# PLL.net
KiCad netlist of a schematic drawn in Altium Designer
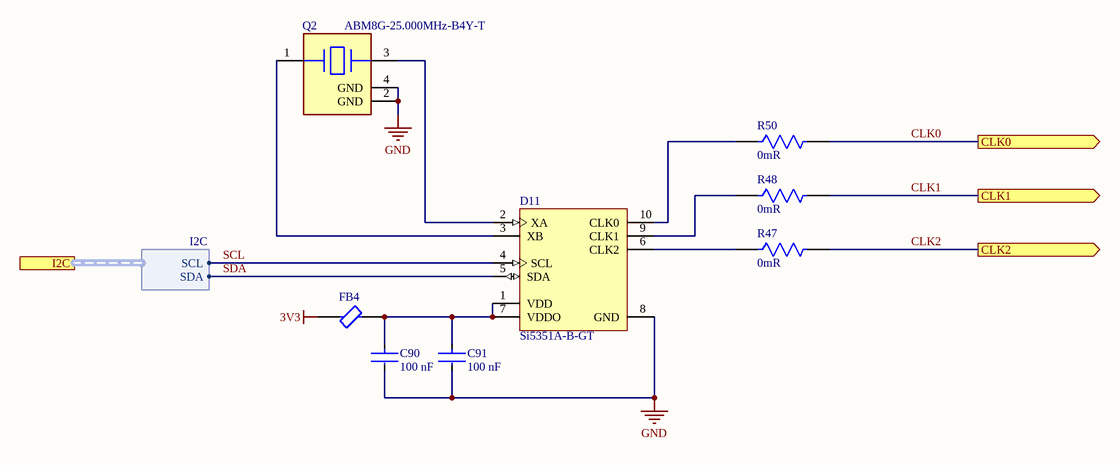
[diagram p0: PLL.SchDoc]

(export (version "E")
  (design (tool "Eeschema 10.0.6"))
  (components
    (comp (ref "C90")
      (value "CC0805KRX7R9BB104")
      (footprint "FP-CC0805-0_85-IPC_A")
      (description "CAP CER 0.1UF 50V X7R 0805")
      (fields (field (name "MANUFACTURER") "Yageo") (field (name "CAPACITANCE") "100 nF"))
      (libsource (lib "zxevo") (part "CMP-2100-03606-3"))
    )
    (comp (ref "C91")
      (value "CC0805KRX7R9BB104")
      (footprint "FP-CC0805-0_85-IPC_A")
      (description "CAP CER 0.1UF 50V X7R 0805")
      (fields (field (name "MANUFACTURER") "Yageo") (field (name "CAPACITANCE") "100 nF"))
      (libsource (lib "zxevo") (part "CMP-2100-03606-3"))
    )
    (comp (ref "D11")
      (value "Si5351A-B-GT")
      (footprint "SLAB-MSOP-10_L")
      (fields
        (field (name "MANUFACTURER") "Silicon Labs")
        (field (name "MANUFACTURER PART NUMBER") "SI5351A-B-GT")
      )
      (libsource (lib "zxevo") (part "CMP-0510-00012-1"))
    )
    (comp (ref "FB4")
      (value "BLM21AG601SN1J")
      (footprint "FP-BLM21-0_2-t0_85-e0_5-IPC_A")
      (description "Chip Ferrite Bead, 0805, 600Ω @ 100MHz, 0.2Ω, 25%, 700mA")
      (fields (field (name "MANUFACTURER") "Murata"))
      (libsource (lib "zxevo") (part "CMP-0686-00643-3"))
    )
    (comp (ref "Q2")
      (value "ABM8G-25.000MHz-B4Y-T")
      (footprint "FP-ABM8G-MFG")
      (description "CRYSTAL 25.0000MHZ 10PF SMD")
      (fields
        (field (name "MANUFACTURER") "Abracon")
        (field (name "MANUFACTURER PART NUMBER") "ABM8G-25.000MHZ-B4Y-T")
      )
      (libsource (lib "zxevo") (part "CMP-27762-000021-1"))
    )
    (comp (ref "R47")
      (value "CR0805-J/-000ELF")
      (footprint "FP-CR0805-IPC_A")
      (description "Thick Film Chip Resistors 0805 0Ω 0.125W 5%")
      (fields (field (name "RESISTANCE") "0mR") (field (name "MANUFACTURER") "Bourns"))
      (libsource (lib "zxevo") (part "CMP-07231-004348-1"))
    )
    (comp (ref "R48")
      (value "CR0805-J/-000ELF")
      (footprint "FP-CR0805-IPC_A")
      (description "Thick Film Chip Resistors 0805 0Ω 0.125W 5%")
      (fields (field (name "RESISTANCE") "0mR") (field (name "MANUFACTURER") "Bourns"))
      (libsource (lib "zxevo") (part "CMP-07231-004348-1"))
    )
    (comp (ref "R50")
      (value "CR0805-J/-000ELF")
      (footprint "FP-CR0805-IPC_A")
      (description "Thick Film Chip Resistors 0805 0Ω 0.125W 5%")
      (fields (field (name "RESISTANCE") "0mR") (field (name "MANUFACTURER") "Bourns"))
      (libsource (lib "zxevo") (part "CMP-07231-004348-1"))
    )
  )
  (nets
    (net (code "2") (name "/CLK0") (class "Default")
      (node (ref "R50") (pin "2") (pinfunction "2_2") (pintype "passive"))
    )
    (net (code "3") (name "/CLK1") (class "Default")
      (node (ref "R48") (pin "2") (pinfunction "2_2") (pintype "passive"))
    )
    (net (code "4") (name "/CLK2") (class "Default")
      (node (ref "R47") (pin "2") (pinfunction "2_2") (pintype "passive"))
    )
    (net (code "5") (name "/SCL") (class "Default")
      (node (ref "D11") (pin "4") (pinfunction "SCL_4") (pintype "input"))
    )
    (net (code "6") (name "/SDA") (class "Default")
      (node (ref "D11") (pin "5") (pinfunction "SDA_5") (pintype "bidirectional"))
    )
    (net (code "8") (name "3V3") (class "Default")
      (node (ref "FB4") (pin "1") (pinfunction "1_1") (pintype "passive"))
    )
    (net (code "9") (name "GND") (class "Default")
      (node (ref "C90") (pin "2") (pinfunction "2_2") (pintype "passive"))
      (node (ref "C91") (pin "2") (pinfunction "2_2") (pintype "passive"))
      (node (ref "D11") (pin "8") (pinfunction "GND_8") (pintype "power_in"))
      (node (ref "Q2") (pin "2") (pinfunction "GND_2") (pintype "power_in"))
      (node (ref "Q2") (pin "4") (pinfunction "GND_4") (pintype "power_in"))
    )
    (net (code "10") (name "Net-(D11-CLK0)") (class "Default")
      (node (ref "D11") (pin "10") (pinfunction "CLK0_10") (pintype "tri_state"))
      (node (ref "R50") (pin "1") (pinfunction "1_1") (pintype "passive"))
    )
    (net (code "11") (name "Net-(D11-CLK1)") (class "Default")
      (node (ref "D11") (pin "9") (pinfunction "CLK1_9") (pintype "tri_state"))
      (node (ref "R48") (pin "1") (pinfunction "1_1") (pintype "passive"))
    )
    (net (code "12") (name "Net-(D11-CLK2)") (class "Default")
      (node (ref "D11") (pin "6") (pinfunction "CLK2_6") (pintype "tri_state"))
      (node (ref "R47") (pin "1") (pinfunction "1_1") (pintype "passive"))
    )
    (net (code "13") (name "Net-(D11-VDD)") (class "Default")
      (node (ref "C90") (pin "1") (pinfunction "1_1") (pintype "passive"))
      (node (ref "C91") (pin "1") (pinfunction "1_1") (pintype "passive"))
      (node (ref "D11") (pin "1") (pinfunction "VDD_1") (pintype "power_in"))
      (node (ref "D11") (pin "7") (pinfunction "VDDO_7") (pintype "power_in"))
      (node (ref "FB4") (pin "2") (pinfunction "2_2") (pintype "passive"))
    )
    (net (code "14") (name "Net-(D11-XA)") (class "Default")
      (node (ref "D11") (pin "2") (pinfunction "XA_2") (pintype "input"))
      (node (ref "Q2") (pin "3") (pinfunction "3_3") (pintype "passive"))
    )
    (net (code "15") (name "Net-(D11-XB)") (class "Default")
      (node (ref "D11") (pin "3") (pinfunction "XB_3") (pintype "passive"))
      (node (ref "Q2") (pin "1") (pinfunction "1_1") (pintype "passive"))
    )
  )
)
